# camera.net
KiCad netlist of a schematic drawn in Altium Designer
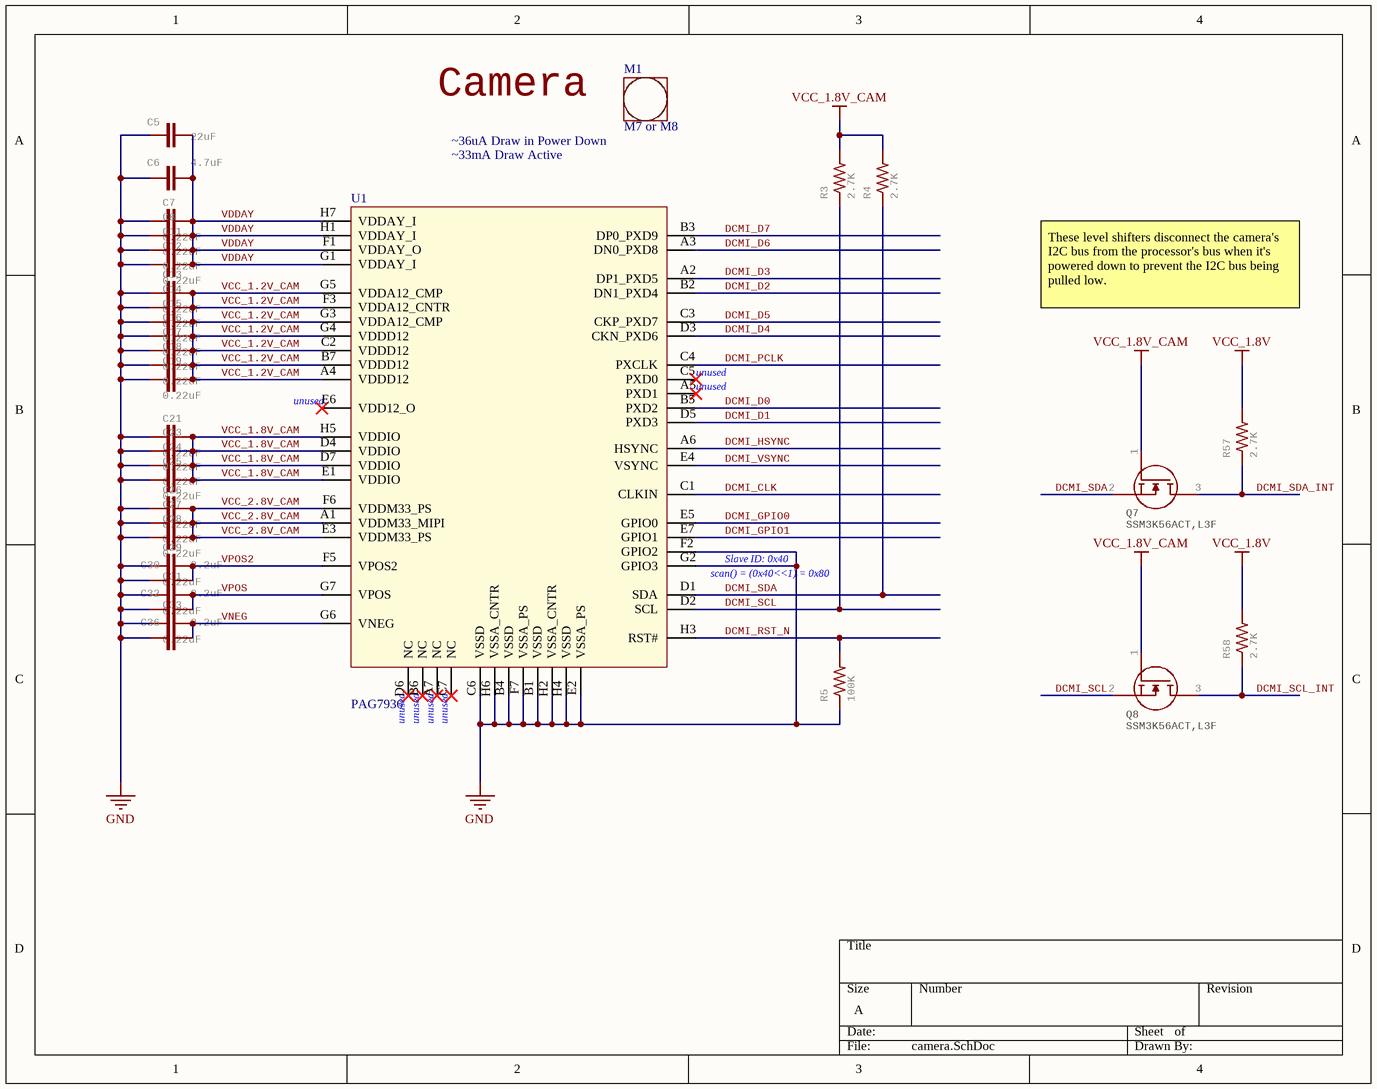
[diagram p0: camera.SchDoc]

(export (version "E")
  (design (tool "Eeschema 10.0.6"))
  (components
    (comp (ref "C5")
      (value "22uF")
      (footprint "0805")
      (fields (field (name "MPN") "CL21A226MQQNNNE"))
      (libsource (lib "openmv-ae3") (part "22UF-0805-6.3V-20%"))
    )
    (comp (ref "C6")
      (value "4.7uF")
      (footprint "0402-CAP")
      (description "0402 (1005 Metric) Nick Garner - TeleSense")
      (fields (field (name "MPN") "JMK105BBJ475MV-F"))
      (libsource (lib "openmv-ae3") (part "CAP_0402"))
    )
    (comp (ref "C7")
      (value "0.22uF")
      (footprint "C0201")
      (description "CAPACITOR, European symbol")
      (fields (field (name "MPN") "GRM033R60J224ME15D"))
      (libsource (lib "openmv-ae3") (part "C-EUC0201"))
    )
    (comp (ref "C8")
      (value "0.22uF")
      (footprint "C0201")
      (description "CAPACITOR, European symbol")
      (fields (field (name "MPN") "GRM033R60J224ME15D"))
      (libsource (lib "openmv-ae3") (part "C-EUC0201"))
    )
    (comp (ref "C11")
      (value "0.22uF")
      (footprint "C0201")
      (description "CAPACITOR, European symbol")
      (fields (field (name "MPN") "GRM033R60J224ME15D"))
      (libsource (lib "openmv-ae3") (part "C-EUC0201"))
    )
    (comp (ref "C12")
      (value "0.22uF")
      (footprint "C0201")
      (description "CAPACITOR, European symbol")
      (fields (field (name "MPN") "GRM033R60J224ME15D"))
      (libsource (lib "openmv-ae3") (part "C-EUC0201"))
    )
    (comp (ref "C13")
      (value "0.22uF")
      (footprint "C0201")
      (description "CAPACITOR, European symbol")
      (fields (field (name "MPN") "GRM033R60J224ME15D"))
      (libsource (lib "openmv-ae3") (part "C-EUC0201"))
    )
    (comp (ref "C14")
      (value "0.22uF")
      (footprint "C0201")
      (description "CAPACITOR, European symbol")
      (fields (field (name "MPN") "GRM033R60J224ME15D"))
      (libsource (lib "openmv-ae3") (part "C-EUC0201"))
    )
    (comp (ref "C15")
      (value "0.22uF")
      (footprint "C0201")
      (description "CAPACITOR, European symbol")
      (fields (field (name "MPN") "GRM033R60J224ME15D"))
      (libsource (lib "openmv-ae3") (part "C-EUC0201"))
    )
    (comp (ref "C16")
      (value "0.22uF")
      (footprint "C0201")
      (description "CAPACITOR, European symbol")
      (fields (field (name "MPN") "GRM033R60J224ME15D"))
      (libsource (lib "openmv-ae3") (part "C-EUC0201"))
    )
    (comp (ref "C17")
      (value "0.22uF")
      (footprint "C0201")
      (description "CAPACITOR, European symbol")
      (fields (field (name "MPN") "GRM033R60J224ME15D"))
      (libsource (lib "openmv-ae3") (part "C-EUC0201"))
    )
    (comp (ref "C18")
      (value "0.22uF")
      (footprint "C0201")
      (description "CAPACITOR, European symbol")
      (fields (field (name "MPN") "GRM033R60J224ME15D"))
      (libsource (lib "openmv-ae3") (part "C-EUC0201"))
    )
    (comp (ref "C19")
      (value "0.22uF")
      (footprint "C0201")
      (description "CAPACITOR, European symbol")
      (fields (field (name "MPN") "GRM033R60J224ME15D"))
      (libsource (lib "openmv-ae3") (part "C-EUC0201"))
    )
    (comp (ref "C21")
      (value "0.22uF")
      (footprint "C0201")
      (description "CAPACITOR, European symbol")
      (fields (field (name "MPN") "GRM033R60J224ME15D"))
      (libsource (lib "openmv-ae3") (part "C-EUC0201"))
    )
    (comp (ref "C23")
      (value "0.22uF")
      (footprint "C0201")
      (description "CAPACITOR, European symbol")
      (fields (field (name "MPN") "GRM033R60J224ME15D"))
      (libsource (lib "openmv-ae3") (part "C-EUC0201"))
    )
    (comp (ref "C24")
      (value "0.22uF")
      (footprint "C0201")
      (description "CAPACITOR, European symbol")
      (fields (field (name "MPN") "GRM033R60J224ME15D"))
      (libsource (lib "openmv-ae3") (part "C-EUC0201"))
    )
    (comp (ref "C25")
      (value "0.22uF")
      (footprint "C0201")
      (description "CAPACITOR, European symbol")
      (fields (field (name "MPN") "GRM033R60J224ME15D"))
      (libsource (lib "openmv-ae3") (part "C-EUC0201"))
    )
    (comp (ref "C26")
      (value "0.22uF")
      (footprint "C0201")
      (description "CAPACITOR, European symbol")
      (fields (field (name "MPN") "GRM033R60J224ME15D"))
      (libsource (lib "openmv-ae3") (part "C-EUC0201"))
    )
    (comp (ref "C27")
      (value "0.22uF")
      (footprint "C0201")
      (description "CAPACITOR, European symbol")
      (fields (field (name "MPN") "GRM033R60J224ME15D"))
      (libsource (lib "openmv-ae3") (part "C-EUC0201"))
    )
    (comp (ref "C28")
      (value "0.22uF")
      (footprint "C0201")
      (description "CAPACITOR, European symbol")
      (fields (field (name "MPN") "GRM033R60J224ME15D"))
      (libsource (lib "openmv-ae3") (part "C-EUC0201"))
    )
    (comp (ref "C29")
      (value "0.22uF")
      (footprint "C0201")
      (description "CAPACITOR, European symbol")
      (fields (field (name "MPN") "GRM033R60J224ME15D"))
      (libsource (lib "openmv-ae3") (part "C-EUC0201"))
    )
    (comp (ref "C30")
      (value "2.2uF")
      (footprint "0402-CAP")
      (description "0402 (1005 Metric) Nick Garner - TeleSense")
      (fields (field (name "MPN") "CL05A225MQ5NNNC"))
      (libsource (lib "openmv-ae3") (part "CAP_0402"))
    )
    (comp (ref "C31")
      (value "0.22uF")
      (footprint "C0201")
      (description "CAPACITOR, European symbol")
      (fields (field (name "MPN") "GRM033R60J224ME15D"))
      (libsource (lib "openmv-ae3") (part "C-EUC0201"))
    )
    (comp (ref "C32")
      (value "2.2uF")
      (footprint "0402-CAP")
      (description "0402 (1005 Metric) Nick Garner - TeleSense")
      (fields (field (name "MPN") "CL05A225MQ5NNNC"))
      (libsource (lib "openmv-ae3") (part "CAP_0402"))
    )
    (comp (ref "C33")
      (value "0.22uF")
      (footprint "C0201")
      (description "CAPACITOR, European symbol")
      (fields (field (name "MPN") "GRM033R60J224ME15D"))
      (libsource (lib "openmv-ae3") (part "C-EUC0201"))
    )
    (comp (ref "C36")
      (value "2.2uF")
      (footprint "0402-CAP")
      (description "0402 (1005 Metric) Nick Garner - TeleSense")
      (fields (field (name "MPN") "CL05A225MQ5NNNC"))
      (libsource (lib "openmv-ae3") (part "CAP_0402"))
    )
    (comp (ref "M1")
      (value "M7 or M8")
      (footprint "M7_M8")
      (libsource (lib "openmv-ae3") (part "M7_M8_LENS_MOUNT"))
    )
    (comp (ref "Q7")
      (value "NMOS")
      (footprint "DFN1006")
      (fields (field (name "MPN") "SSM3K56ACT,L3F") (field (name "PART NUMBER") "SSM3K56ACT,L3F"))
      (libsource (lib "openmv-ae3") (part "NMOS"))
    )
    (comp (ref "Q8")
      (value "NMOS")
      (footprint "DFN1006")
      (fields (field (name "MPN") "SSM3K56ACT,L3F") (field (name "PART NUMBER") "SSM3K56ACT,L3F"))
      (libsource (lib "openmv-ae3") (part "NMOS"))
    )
    (comp (ref "R3")
      (value "2.7K")
      (footprint "R0201")
      (fields (field (name "MPN") "RC0201JR-072K7L") (field (name "LIBRARYNAME") "sfe"))
      (libsource (lib "openmv-ae3") (part "RESISTOR0402-RES"))
    )
    (comp (ref "R4")
      (value "2.7K")
      (footprint "R0201")
      (fields (field (name "MPN") "RC0201JR-072K7L") (field (name "LIBRARYNAME") "sfe"))
      (libsource (lib "openmv-ae3") (part "RESISTOR0402-RES"))
    )
    (comp (ref "R5")
      (value "100K")
      (footprint "R0201")
      (fields (field (name "MPN") "RMCF0201FT100K") (field (name "LIBRARYNAME") "sfe"))
      (libsource (lib "openmv-ae3") (part "RESISTOR0402-RES"))
    )
    (comp (ref "R57")
      (value "2.7K")
      (footprint "R0201")
      (fields (field (name "MPN") "RC0201JR-072K7L") (field (name "LIBRARYNAME") "sfe"))
      (libsource (lib "openmv-ae3") (part "RESISTOR0402-RES"))
    )
    (comp (ref "R58")
      (value "2.7K")
      (footprint "R0201")
      (fields (field (name "MPN") "RC0201JR-072K7L") (field (name "LIBRARYNAME") "sfe"))
      (libsource (lib "openmv-ae3") (part "RESISTOR0402-RES"))
    )
    (comp (ref "U1")
      (value "PAG7936")
      (footprint "PAG7936")
      (fields (field (name "MF") "PixArt") (field (name "MPN") "PAG7936"))
      (libsource (lib "openmv-ae3") (part "PAG7936"))
    )
  )
  (nets
    (net (code "1") (name "/DCMI_CLK") (class "Default")
      (node (ref "U1") (pin "C1") (pinfunction "CLKIN_C1") (pintype "passive"))
    )
    (net (code "2") (name "/DCMI_D0") (class "Default")
      (node (ref "U1") (pin "B5") (pinfunction "PXD2_B5") (pintype "passive"))
    )
    (net (code "3") (name "/DCMI_D1") (class "Default")
      (node (ref "U1") (pin "D5") (pinfunction "PXD3_D5") (pintype "passive"))
    )
    (net (code "4") (name "/DCMI_D2") (class "Default")
      (node (ref "U1") (pin "B2") (pinfunction "DN1_PXD4_B2") (pintype "passive"))
    )
    (net (code "5") (name "/DCMI_D3") (class "Default")
      (node (ref "U1") (pin "A2") (pinfunction "DP1_PXD5_A2") (pintype "passive"))
    )
    (net (code "6") (name "/DCMI_D4") (class "Default")
      (node (ref "U1") (pin "D3") (pinfunction "CKN_PXD6_D3") (pintype "passive"))
    )
    (net (code "7") (name "/DCMI_D5") (class "Default")
      (node (ref "U1") (pin "C3") (pinfunction "CKP_PXD7_C3") (pintype "passive"))
    )
    (net (code "8") (name "/DCMI_D6") (class "Default")
      (node (ref "U1") (pin "A3") (pinfunction "DN0_PXD8_A3") (pintype "passive"))
    )
    (net (code "9") (name "/DCMI_D7") (class "Default")
      (node (ref "U1") (pin "B3") (pinfunction "DP0_PXD9_B3") (pintype "passive"))
    )
    (net (code "10") (name "/DCMI_GPIO0") (class "Default")
      (node (ref "U1") (pin "E5") (pinfunction "GPIO0_E5") (pintype "passive"))
    )
    (net (code "11") (name "/DCMI_GPIO1") (class "Default")
      (node (ref "U1") (pin "E7") (pinfunction "GPIO1_E7") (pintype "passive"))
    )
    (net (code "12") (name "/DCMI_HSYNC") (class "Default")
      (node (ref "U1") (pin "A6") (pinfunction "HSYNC_A6") (pintype "passive"))
    )
    (net (code "13") (name "/DCMI_PCLK") (class "Default")
      (node (ref "U1") (pin "C4") (pinfunction "PXCLK_C4") (pintype "passive"))
    )
    (net (code "14") (name "/DCMI_RST_N") (class "Default")
      (node (ref "R5") (pin "2") (pinfunction "2_2") (pintype "passive"))
      (node (ref "U1") (pin "H3") (pinfunction "RST#_H3") (pintype "passive"))
    )
    (net (code "15") (name "/DCMI_SCL") (class "Default")
      (node (ref "Q8") (pin "2") (pinfunction "S_2") (pintype "bidirectional"))
      (node (ref "R3") (pin "1") (pinfunction "1_1") (pintype "passive"))
      (node (ref "U1") (pin "D2") (pinfunction "SCL_D2") (pintype "passive"))
    )
    (net (code "16") (name "/DCMI_SCL_INT") (class "Default")
      (node (ref "Q8") (pin "3") (pinfunction "D_3") (pintype "bidirectional"))
      (node (ref "R58") (pin "1") (pinfunction "1_1") (pintype "passive"))
    )
    (net (code "17") (name "/DCMI_SDA") (class "Default")
      (node (ref "Q7") (pin "2") (pinfunction "S_2") (pintype "bidirectional"))
      (node (ref "R4") (pin "1") (pinfunction "1_1") (pintype "passive"))
      (node (ref "U1") (pin "D1") (pinfunction "SDA_D1") (pintype "passive"))
    )
    (net (code "18") (name "/DCMI_SDA_INT") (class "Default")
      (node (ref "Q7") (pin "3") (pinfunction "D_3") (pintype "bidirectional"))
      (node (ref "R57") (pin "1") (pinfunction "1_1") (pintype "passive"))
    )
    (net (code "19") (name "/DCMI_VSYNC") (class "Default")
      (node (ref "U1") (pin "E4") (pinfunction "VSYNC_E4") (pintype "passive"))
    )
    (net (code "20") (name "/VCC_1.2V_CAM") (class "Default")
      (node (ref "C13") (pin "2") (pinfunction "2_2") (pintype "passive"))
      (node (ref "C14") (pin "2") (pinfunction "2_2") (pintype "passive"))
      (node (ref "C15") (pin "2") (pinfunction "2_2") (pintype "passive"))
      (node (ref "C16") (pin "2") (pinfunction "2_2") (pintype "passive"))
      (node (ref "C17") (pin "2") (pinfunction "2_2") (pintype "passive"))
      (node (ref "C18") (pin "2") (pinfunction "2_2") (pintype "passive"))
      (node (ref "C19") (pin "2") (pinfunction "2_2") (pintype "passive"))
      (node (ref "U1") (pin "A4") (pinfunction "VDDD12_A4") (pintype "passive"))
      (node (ref "U1") (pin "B7") (pinfunction "VDDD12_B7") (pintype "passive"))
      (node (ref "U1") (pin "C2") (pinfunction "VDDD12_C2") (pintype "passive"))
      (node (ref "U1") (pin "F3") (pinfunction "VDDA12_CNTR_F3") (pintype "passive"))
      (node (ref "U1") (pin "G3") (pinfunction "VDDA12_CMP_G3") (pintype "passive"))
      (node (ref "U1") (pin "G4") (pinfunction "VDDD12_G4") (pintype "passive"))
      (node (ref "U1") (pin "G5") (pinfunction "VDDA12_CMP_G5") (pintype "passive"))
    )
    (net (code "21") (name "/VCC_2.8V_CAM") (class "Default")
      (node (ref "C26") (pin "2") (pinfunction "2_2") (pintype "passive"))
      (node (ref "C27") (pin "2") (pinfunction "2_2") (pintype "passive"))
      (node (ref "C28") (pin "2") (pinfunction "2_2") (pintype "passive"))
      (node (ref "U1") (pin "A1") (pinfunction "VDDM33_MIPI_A1") (pintype "passive"))
      (node (ref "U1") (pin "E3") (pinfunction "VDDM33_PS_E3") (pintype "passive"))
      (node (ref "U1") (pin "F6") (pinfunction "VDDM33_PS_F6") (pintype "passive"))
    )
    (net (code "22") (name "/VDDAY") (class "Default")
      (node (ref "C11") (pin "2") (pinfunction "2_2") (pintype "passive"))
      (node (ref "C12") (pin "2") (pinfunction "2_2") (pintype "passive"))
      (node (ref "C5") (pin "2") (pinfunction "2_2") (pintype "passive"))
      (node (ref "C6") (pin "2") (pinfunction "2_2") (pintype "passive"))
      (node (ref "C7") (pin "2") (pinfunction "2_2") (pintype "passive"))
      (node (ref "C8") (pin "2") (pinfunction "2_2") (pintype "passive"))
      (node (ref "U1") (pin "F1") (pinfunction "VDDAY_O_F1") (pintype "passive"))
      (node (ref "U1") (pin "G1") (pinfunction "VDDAY_I_G1") (pintype "passive"))
      (node (ref "U1") (pin "H1") (pinfunction "VDDAY_I_H1") (pintype "passive"))
      (node (ref "U1") (pin "H7") (pinfunction "VDDAY_I_H7") (pintype "passive"))
    )
    (net (code "23") (name "/VNEG") (class "Default")
      (node (ref "C33") (pin "2") (pinfunction "2_2") (pintype "passive"))
      (node (ref "C36") (pin "2") (pinfunction "2_2") (pintype "passive"))
      (node (ref "U1") (pin "G6") (pinfunction "VNEG_G6") (pintype "passive"))
    )
    (net (code "24") (name "/VPOS") (class "Default")
      (node (ref "C31") (pin "2") (pinfunction "2_2") (pintype "passive"))
      (node (ref "C32") (pin "2") (pinfunction "2_2") (pintype "passive"))
      (node (ref "U1") (pin "G7") (pinfunction "VPOS_G7") (pintype "passive"))
    )
    (net (code "25") (name "/VPOS2") (class "Default")
      (node (ref "C29") (pin "2") (pinfunction "2_2") (pintype "passive"))
      (node (ref "C30") (pin "2") (pinfunction "2_2") (pintype "passive"))
      (node (ref "U1") (pin "F5") (pinfunction "VPOS2_F5") (pintype "passive"))
    )
    (net (code "26") (name "GND") (class "Default")
      (node (ref "C11") (pin "1") (pinfunction "1_1") (pintype "passive"))
      (node (ref "C12") (pin "1") (pinfunction "1_1") (pintype "passive"))
      (node (ref "C13") (pin "1") (pinfunction "1_1") (pintype "passive"))
      (node (ref "C14") (pin "1") (pinfunction "1_1") (pintype "passive"))
      (node (ref "C15") (pin "1") (pinfunction "1_1") (pintype "passive"))
      (node (ref "C16") (pin "1") (pinfunction "1_1") (pintype "passive"))
      (node (ref "C17") (pin "1") (pinfunction "1_1") (pintype "passive"))
      (node (ref "C18") (pin "1") (pinfunction "1_1") (pintype "passive"))
      (node (ref "C19") (pin "1") (pinfunction "1_1") (pintype "passive"))
      (node (ref "C21") (pin "1") (pinfunction "1_1") (pintype "passive"))
      (node (ref "C23") (pin "1") (pinfunction "1_1") (pintype "passive"))
      (node (ref "C24") (pin "1") (pinfunction "1_1") (pintype "passive"))
      (node (ref "C25") (pin "1") (pinfunction "1_1") (pintype "passive"))
      (node (ref "C26") (pin "1") (pinfunction "1_1") (pintype "passive"))
      (node (ref "C27") (pin "1") (pinfunction "1_1") (pintype "passive"))
      (node (ref "C28") (pin "1") (pinfunction "1_1") (pintype "passive"))
      (node (ref "C29") (pin "1") (pinfunction "1_1") (pintype "passive"))
      (node (ref "C30") (pin "1") (pinfunction "1_1") (pintype "passive"))
      (node (ref "C31") (pin "1") (pinfunction "1_1") (pintype "passive"))
      (node (ref "C32") (pin "1") (pinfunction "1_1") (pintype "passive"))
      (node (ref "C33") (pin "1") (pinfunction "1_1") (pintype "passive"))
      (node (ref "C36") (pin "1") (pinfunction "1_1") (pintype "passive"))
      (node (ref "C5") (pin "1") (pinfunction "1_1") (pintype "passive"))
      (node (ref "C6") (pin "1") (pinfunction "1_1") (pintype "passive"))
      (node (ref "C7") (pin "1") (pinfunction "1_1") (pintype "passive"))
      (node (ref "C8") (pin "1") (pinfunction "1_1") (pintype "passive"))
      (node (ref "R5") (pin "1") (pinfunction "1_1") (pintype "passive"))
      (node (ref "U1") (pin "B1") (pinfunction "VSSD_B1") (pintype "passive"))
      (node (ref "U1") (pin "B4") (pinfunction "VSSD_B4") (pintype "passive"))
      (node (ref "U1") (pin "C6") (pinfunction "VSSD_C6") (pintype "passive"))
      (node (ref "U1") (pin "E2") (pinfunction "VSSA_PS_E2") (pintype "passive"))
      (node (ref "U1") (pin "F2") (pinfunction "GPIO2_F2") (pintype "passive"))
      (node (ref "U1") (pin "F7") (pinfunction "VSSA_PS_F7") (pintype "passive"))
      (node (ref "U1") (pin "G2") (pinfunction "GPIO3_G2") (pintype "passive"))
      (node (ref "U1") (pin "H2") (pinfunction "VSSA_CNTR_H2") (pintype "passive"))
      (node (ref "U1") (pin "H4") (pinfunction "VSSD_H4") (pintype "passive"))
      (node (ref "U1") (pin "H6") (pinfunction "VSSA_CNTR_H6") (pintype "passive"))
    )
    (net (code "27") (name "VCC_1.8V") (class "Default")
      (node (ref "R57") (pin "2") (pinfunction "2_2") (pintype "passive"))
      (node (ref "R58") (pin "2") (pinfunction "2_2") (pintype "passive"))
    )
    (net (code "28") (name "VCC_1.8V_CAM") (class "Default")
      (node (ref "C21") (pin "2") (pinfunction "2_2") (pintype "passive"))
      (node (ref "C23") (pin "2") (pinfunction "2_2") (pintype "passive"))
      (node (ref "C24") (pin "2") (pinfunction "2_2") (pintype "passive"))
      (node (ref "C25") (pin "2") (pinfunction "2_2") (pintype "passive"))
      (node (ref "Q7") (pin "1") (pinfunction "G_1") (pintype "bidirectional"))
      (node (ref "Q8") (pin "1") (pinfunction "G_1") (pintype "bidirectional"))
      (node (ref "R3") (pin "2") (pinfunction "2_2") (pintype "passive"))
      (node (ref "R4") (pin "2") (pinfunction "2_2") (pintype "passive"))
      (node (ref "U1") (pin "D4") (pinfunction "VDDIO_D4") (pintype "passive"))
      (node (ref "U1") (pin "D7") (pinfunction "VDDIO_D7") (pintype "passive"))
      (node (ref "U1") (pin "E1") (pinfunction "VDDIO_E1") (pintype "passive"))
      (node (ref "U1") (pin "H5") (pinfunction "VDDIO_H5") (pintype "passive"))
    )
    (net (code "29") (name "unconnected-(U1-NC-PadA7)") (class "Default")
      (node (ref "U1") (pin "A7") (pinfunction "NC_A7") (pintype "passive+no_connect"))
    )
    (net (code "30") (name "unconnected-(U1-NC-PadB6)") (class "Default")
      (node (ref "U1") (pin "B6") (pinfunction "NC_B6") (pintype "passive+no_connect"))
    )
    (net (code "31") (name "unconnected-(U1-NC-PadC7)") (class "Default")
      (node (ref "U1") (pin "C7") (pinfunction "NC_C7") (pintype "passive+no_connect"))
    )
    (net (code "32") (name "unconnected-(U1-NC-PadD6)") (class "Default")
      (node (ref "U1") (pin "D6") (pinfunction "NC_D6") (pintype "passive+no_connect"))
    )
    (net (code "33") (name "unconnected-(U1-PXD0-PadC5)") (class "Default")
      (node (ref "U1") (pin "C5") (pinfunction "PXD0_C5") (pintype "passive+no_connect"))
    )
    (net (code "34") (name "unconnected-(U1-PXD1-PadA5)") (class "Default")
      (node (ref "U1") (pin "A5") (pinfunction "PXD1_A5") (pintype "passive+no_connect"))
    )
    (net (code "35") (name "unconnected-(U1-VDD12_O-PadE6)") (class "Default")
      (node (ref "U1") (pin "E6") (pinfunction "VDD12_O_E6") (pintype "passive+no_connect"))
    )
  )
)
